# 07_Power_Supply.net
KiCad netlist of a schematic drawn in Altium Designer
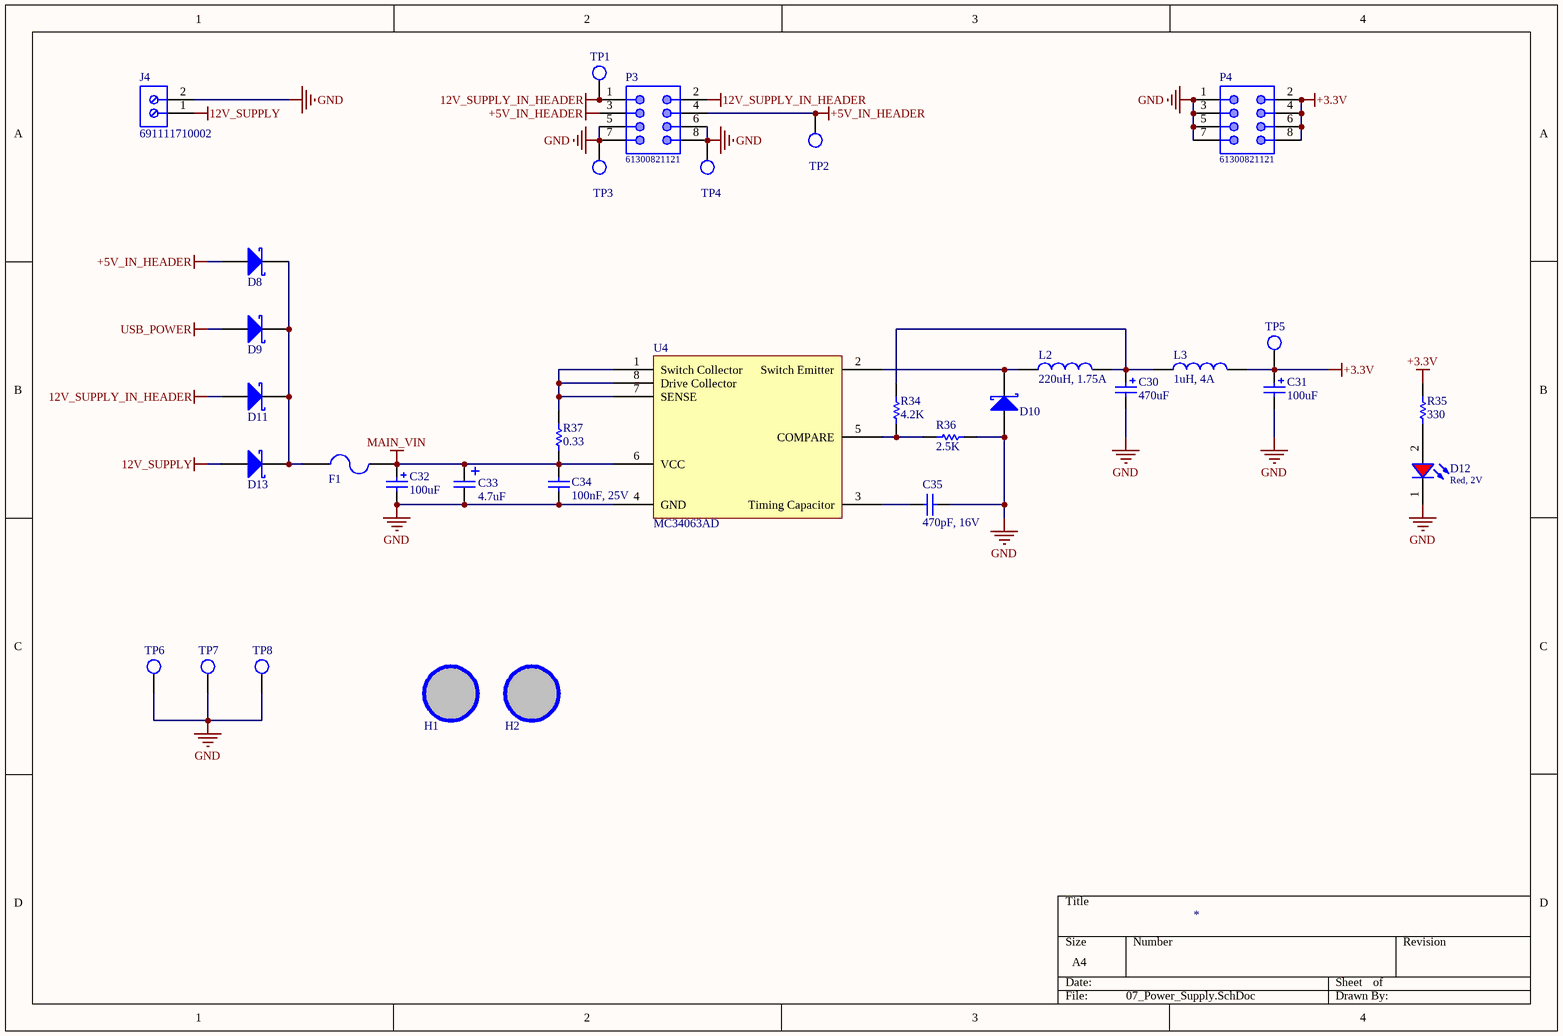
[diagram p0: 07_Power_Supply.SchDoc]

(export (version "E")
  (design (tool "Eeschema 10.0.6"))
  (components
    (comp (ref "C30")
      (value "470uF")
      (footprint "CAP ALU SIZE F")
      (description "Polarized Capacitor (Radial)")
      (fields (field (name "Comment") "Cap Pol SMD"))
      (libsource (lib "PIF_Library") (part "Cap Pol SMD"))
    )
    (comp (ref "C31")
      (value "100uF")
      (footprint "CAP ALU SIZE D")
      (description "Polarized Capacitor (Radial)")
      (fields (field (name "Comment") "Cap Pol SMD"))
      (libsource (lib "PIF_Library") (part "Cap Pol SMD"))
    )
    (comp (ref "C32")
      (value "100uF")
      (footprint "CAP ALU SIZE D")
      (description "Polarized Capacitor (Radial)")
      (fields (field (name "Comment") "Cap Pol SMD"))
      (libsource (lib "PIF_Library") (part "Cap Pol SMD"))
    )
    (comp (ref "C33")
      (value "4.7uF")
      (footprint "CAPMP3216X18N")
      (fields (field (name "Comment") "Tantalum Capacitor"))
      (libsource (lib "MiclsLib") (part "Tantalum Capacitor"))
    )
    (comp (ref "C34")
      (value "100nF, 25V")
      (footprint "WCAP-CSGP_0603_H=0.8mm_Reflow")
      (description "WCAP-CSGP Multilayer Ceramic Chip Capacitor, General Purpose, size 0603, X7R, 100nF, 25V")
      (fields
        (field (name "MANUFACTURER PART NUMBER") "885012206071")
        (field (name "MANUFACTURER") "Wurth Elektronik")
      )
      (libsource (lib "Altium_WCAP-CSGP (rev20a)") (part "885012206071"))
    )
    (comp (ref "C35")
      (value "470pF, 16V")
      (footprint "WCAP-CSGP_0603_H=0.8mm_Reflow")
      (description "WCAP-CSGP Multilayer Ceramic Chip Capacitor, General Purpose, size 0603, NP0, 470pF, 16V")
      (fields
        (field (name "MANUFACTURER PART NUMBER") "885012006027")
        (field (name "MANUFACTURER") "Wurth Elektronik")
      )
      (libsource (lib "Altium_WCAP-CSGP (rev20a)") (part "885012006027"))
    )
    (comp (ref "D8")
      (value "D Schottky")
      (footprint "SS34")
      (description "Schottky Diode")
      (fields (field (name "PUBLISHER") "Altium Limited"))
      (libsource (lib "PIF_Library") (part "D Schottky"))
    )
    (comp (ref "D9")
      (value "D Schottky")
      (footprint "SS34")
      (description "Schottky Diode")
      (fields (field (name "PUBLISHER") "Altium Limited"))
      (libsource (lib "PIF_Library") (part "D Schottky"))
    )
    (comp (ref "D10")
      (value "D Schottky")
      (footprint "SS34")
      (description "Schottky Diode")
      (fields (field (name "PUBLISHER") "Altium Limited"))
      (libsource (lib "PIF_Library") (part "D Schottky"))
    )
    (comp (ref "D11")
      (value "D Schottky")
      (footprint "SS34")
      (description "Schottky Diode")
      (fields (field (name "PUBLISHER") "Altium Limited"))
      (libsource (lib "PIF_Library") (part "D Schottky"))
    )
    (comp (ref "D12")
      (value "Red, 2V")
      (footprint "WL-SMCW_0603_H=0.7mm")
      (description "WL-SMCW SMT Mono-color Chip LED Waterclear, size 0603, Red, 2V, 140deg")
      (fields (field (name "PART NUMBER") "150060RS75000") (field (name "PUBLISHER") "Wurth Elektronik"))
      (libsource (lib "Altium_WL-SMCW (rev20a)") (part "150060RS75000"))
    )
    (comp (ref "D13")
      (value "D Schottky")
      (footprint "SS34")
      (description "Schottky Diode")
      (fields (field (name "PUBLISHER") "Altium Limited"))
      (libsource (lib "PIF_Library") (part "D Schottky"))
    )
    (comp (ref "F1") (value "Fuse") (footprint "FUSE SMD") (libsource (lib "PIF_Library") (part "Fuse")))
    (comp (ref "H1")
      (value "Hole")
      (footprint "LO KHOAN 3MM")
      (description "Hole 3mm")
      (libsource (lib "PIF_Library") (part "Hole"))
    )
    (comp (ref "H2")
      (value "Hole")
      (footprint "LO KHOAN 3MM")
      (description "Hole 3mm")
      (libsource (lib "PIF_Library") (part "Hole"))
    )
    (comp (ref "J4")
      (value "691111710002")
      (footprint "691111710002")
      (description "WR-TBL Serie 111 Horizontal Entry Modular, Pressure Clamp, pitch 5mm, 2p")
      (fields (field (name "PUBLISHER") "Wurth Elektronik"))
      (libsource (lib "691322310002.") (part "691111710002"))
    )
    (comp (ref "L2")
      (value "220uH, 1.75A")
      (footprint "WE-PD2A_5848")
      (description "WE-PD2A SMT Power Inductor, size 5848, 220uH, 0.41A")
      (fields
        (field (name "MANUFACTURER PART NUMBER") "784774222")
        (field (name "MANUFACTURER") "Wurth Elektronik")
      )
      (libsource (lib "Altium_WE-PD2A (rev20a)") (part "784774222"))
    )
    (comp (ref "L3")
      (value "1uH, 4A")
      (footprint "WE-PD2A_4532")
      (description "WE-PD2A SMT Power Inductor, size 4532, 1uH, 4A")
      (fields
        (field (name "MANUFACTURER PART NUMBER") "7847730")
        (field (name "MANUFACTURER") "Wurth Elektronik")
      )
      (libsource (lib "Altium_WE-PD2A (rev20a)") (part "7847730"))
    )
    (comp (ref "P3")
      (value "61300821121")
      (footprint "61300821121")
      (description "WR-PHD Pin Header, THT, pitch 2.54mm, Dual Row, Vertical, 8p")
      (fields (field (name "MANUFACTURER") "Wurth Elektronik"))
      (libsource (lib "Altium_WR-PHD (rev20a)") (part "61300821121"))
    )
    (comp (ref "P4")
      (value "61300821121")
      (footprint "61300821121")
      (description "WR-PHD Pin Header, THT, pitch 2.54mm, Dual Row, Vertical, 8p")
      (fields (field (name "MANUFACTURER") "Wurth Elektronik"))
      (libsource (lib "Altium_WR-PHD (rev20a)") (part "61300821121"))
    )
    (comp (ref "R34")
      (value "4.2K")
      (footprint "RES-SM-0603")
      (description "Resistor")
      (fields (field (name "Comment") "RESISTOR SMD"))
      (libsource (lib "PIF_Library") (part "RESISTOR SMD"))
    )
    (comp (ref "R35")
      (value "330")
      (footprint "RES-SM-0603")
      (description "Resistor")
      (fields (field (name "Comment") "RESISTOR SMD"))
      (libsource (lib "PIF_Library") (part "RESISTOR SMD"))
    )
    (comp (ref "R36")
      (value "2.5K")
      (footprint "RES-SM-0603")
      (description "Resistor")
      (fields (field (name "Comment") "RESISTOR SMD"))
      (libsource (lib "PIF_Library") (part "RESISTOR SMD"))
    )
    (comp (ref "R37")
      (value "0.33")
      (footprint "RES-SM-0805")
      (description "Resistor")
      (fields (field (name "Comment") "RESISTOR SMD"))
      (libsource (lib "PIF_Library") (part "RESISTOR SMD"))
    )
    (comp (ref "TP1") (value "Test point") (footprint "TP") (libsource (lib "MiclsLib") (part "TP")))
    (comp (ref "TP2") (value "Test point") (footprint "TP") (libsource (lib "MiclsLib") (part "TP")))
    (comp (ref "TP3") (value "Test point") (footprint "TP") (libsource (lib "MiclsLib") (part "TP")))
    (comp (ref "TP4") (value "Test point") (footprint "TP") (libsource (lib "MiclsLib") (part "TP")))
    (comp (ref "TP5") (value "Test point") (footprint "TP") (libsource (lib "MiclsLib") (part "TP")))
    (comp (ref "TP6") (value "Test point") (footprint "TP") (libsource (lib "MiclsLib") (part "TP")))
    (comp (ref "TP7") (value "Test point") (footprint "TP") (libsource (lib "MiclsLib") (part "TP")))
    (comp (ref "TP8") (value "Test point") (footprint "TP") (libsource (lib "MiclsLib") (part "TP")))
    (comp (ref "U4")
      (value "MC34063AD")
      (footprint "SOIC127P600X170-8N")
      (description "1.5-A boost, buck, inverting switching regulator, operation from 0°C to 70°C")
      (fields (field (name "MANUFACTURER") "Texas Instruments"))
      (libsource (lib "PowerSupply") (part "MC34063"))
    )
  )
  (nets
    (net (code "1") (name "+3.3V") (class "Default")
      (node (ref "C31") (pin "1") (pinfunction "1_1") (pintype "passive"))
      (node (ref "L3") (pin "2") (pinfunction "2_2") (pintype "passive"))
      (node (ref "P4") (pin "2") (pinfunction "2_2") (pintype "passive"))
      (node (ref "P4") (pin "4") (pinfunction "4_4") (pintype "passive"))
      (node (ref "P4") (pin "6") (pinfunction "6_6") (pintype "passive"))
      (node (ref "P4") (pin "8") (pinfunction "8_8") (pintype "passive"))
      (node (ref "R35") (pin "2") (pinfunction "2_2") (pintype "passive"))
      (node (ref "TP5") (pin "1") (pinfunction "27_1") (pintype "passive"))
    )
    (net (code "2") (name "+5V_IN_HEADER") (class "Default")
      (node (ref "D8") (pin "1") (pinfunction "A_1") (pintype "passive"))
      (node (ref "P3") (pin "3") (pinfunction "3_3") (pintype "passive"))
      (node (ref "P3") (pin "4") (pinfunction "4_4") (pintype "passive"))
      (node (ref "TP2") (pin "1") (pinfunction "27_1") (pintype "passive"))
    )
    (net (code "3") (name "12V_SUPPLY") (class "Default")
      (node (ref "D13") (pin "1") (pinfunction "A_1") (pintype "passive"))
      (node (ref "J4") (pin "1") (pinfunction "1_1") (pintype "passive"))
    )
    (net (code "4") (name "12V_SUPPLY_IN_HEADER") (class "Default")
      (node (ref "D11") (pin "1") (pinfunction "A_1") (pintype "passive"))
      (node (ref "P3") (pin "1") (pinfunction "1_1") (pintype "passive"))
      (node (ref "P3") (pin "2") (pinfunction "2_2") (pintype "passive"))
      (node (ref "TP1") (pin "1") (pinfunction "27_1") (pintype "passive"))
    )
    (net (code "5") (name "GND") (class "Default")
      (node (ref "C30") (pin "2") (pinfunction "2_2") (pintype "passive"))
      (node (ref "C31") (pin "2") (pinfunction "2_2") (pintype "passive"))
      (node (ref "C32") (pin "2") (pinfunction "2_2") (pintype "passive"))
      (node (ref "C33") (pin "2") (pinfunction "2_2") (pintype "passive"))
      (node (ref "C34") (pin "1") (pinfunction "1_1") (pintype "passive"))
      (node (ref "C35") (pin "2") (pinfunction "2_2") (pintype "passive"))
      (node (ref "D10") (pin "1") (pinfunction "A_1") (pintype "passive"))
      (node (ref "D12") (pin "1") (pinfunction "K_1") (pintype "passive"))
      (node (ref "J4") (pin "2") (pinfunction "2_2") (pintype "passive"))
      (node (ref "P3") (pin "5") (pinfunction "5_5") (pintype "passive"))
      (node (ref "P3") (pin "6") (pinfunction "6_6") (pintype "passive"))
      (node (ref "P3") (pin "7") (pinfunction "7_7") (pintype "passive"))
      (node (ref "P3") (pin "8") (pinfunction "8_8") (pintype "passive"))
      (node (ref "P4") (pin "1") (pinfunction "1_1") (pintype "passive"))
      (node (ref "P4") (pin "3") (pinfunction "3_3") (pintype "passive"))
      (node (ref "P4") (pin "5") (pinfunction "5_5") (pintype "passive"))
      (node (ref "P4") (pin "7") (pinfunction "7_7") (pintype "passive"))
      (node (ref "R36") (pin "1") (pinfunction "1_1") (pintype "passive"))
      (node (ref "TP3") (pin "1") (pinfunction "27_1") (pintype "passive"))
      (node (ref "TP4") (pin "1") (pinfunction "27_1") (pintype "passive"))
      (node (ref "TP6") (pin "1") (pinfunction "27_1") (pintype "passive"))
      (node (ref "TP7") (pin "1") (pinfunction "27_1") (pintype "passive"))
      (node (ref "TP8") (pin "1") (pinfunction "27_1") (pintype "passive"))
      (node (ref "U4") (pin "4") (pinfunction "GND_4") (pintype "passive"))
    )
    (net (code "6") (name "MAIN_VIN") (class "Default")
      (node (ref "C32") (pin "1") (pinfunction "1_1") (pintype "passive"))
      (node (ref "C33") (pin "1") (pinfunction "1_1") (pintype "passive"))
      (node (ref "C34") (pin "2") (pinfunction "2_2") (pintype "passive"))
      (node (ref "F1") (pin "2") (pinfunction "2_2") (pintype "passive"))
      (node (ref "R37") (pin "1") (pinfunction "1_1") (pintype "passive"))
      (node (ref "U4") (pin "6") (pinfunction "VCC_6") (pintype "passive"))
    )
    (net (code "7") (name "Net-(C30-Pad1)") (class "Default")
      (node (ref "C30") (pin "1") (pinfunction "1_1") (pintype "passive"))
      (node (ref "L2") (pin "2") (pinfunction "2_2") (pintype "passive"))
      (node (ref "L3") (pin "1") (pinfunction "1_1") (pintype "passive"))
      (node (ref "R34") (pin "2") (pinfunction "2_2") (pintype "passive"))
    )
    (net (code "8") (name "Net-(D10-K)") (class "Default")
      (node (ref "D10") (pin "2") (pinfunction "K_2") (pintype "passive"))
      (node (ref "L2") (pin "1") (pinfunction "1_1") (pintype "passive"))
      (node (ref "U4") (pin "2") (pinfunction "Switch_Emitter_2") (pintype "passive"))
    )
    (net (code "9") (name "Net-(D11-K)") (class "Default")
      (node (ref "D11") (pin "2") (pinfunction "K_2") (pintype "passive"))
      (node (ref "D13") (pin "2") (pinfunction "K_2") (pintype "passive"))
      (node (ref "D8") (pin "2") (pinfunction "K_2") (pintype "passive"))
      (node (ref "D9") (pin "2") (pinfunction "K_2") (pintype "passive"))
      (node (ref "F1") (pin "1") (pinfunction "1_1") (pintype "passive"))
    )
    (net (code "10") (name "Net-(D12-A)") (class "Default")
      (node (ref "D12") (pin "2") (pinfunction "A_2") (pintype "passive"))
      (node (ref "R35") (pin "1") (pinfunction "1_1") (pintype "passive"))
    )
    (net (code "11") (name "Net-(U4-COMPARE)") (class "Default")
      (node (ref "R34") (pin "1") (pinfunction "1_1") (pintype "passive"))
      (node (ref "R36") (pin "2") (pinfunction "2_2") (pintype "passive"))
      (node (ref "U4") (pin "5") (pinfunction "COMPARE_5") (pintype "passive"))
    )
    (net (code "12") (name "Net-(U4-Drive_Collector)") (class "Default")
      (node (ref "R37") (pin "2") (pinfunction "2_2") (pintype "passive"))
      (node (ref "U4") (pin "1") (pinfunction "Switch_Collector_1") (pintype "passive"))
      (node (ref "U4") (pin "7") (pinfunction "SENSE_7") (pintype "passive"))
      (node (ref "U4") (pin "8") (pinfunction "Drive_Collector_8") (pintype "passive"))
    )
    (net (code "13") (name "Net-(U4-Timing_Capacitor)") (class "Default")
      (node (ref "C35") (pin "1") (pinfunction "1_1") (pintype "passive"))
      (node (ref "U4") (pin "3") (pinfunction "Timing_Capacitor_3") (pintype "passive"))
    )
    (net (code "14") (name "USB_POWER") (class "Default")
      (node (ref "D9") (pin "1") (pinfunction "A_1") (pintype "passive"))
    )
    (net (code "15") (name "unconnected-(H1-Pad1)") (class "Default")
      (node (ref "H1") (pin "1") (pinfunction "1_1") (pintype "passive"))
    )
    (net (code "16") (name "unconnected-(H2-Pad1)") (class "Default")
      (node (ref "H2") (pin "1") (pinfunction "1_1") (pintype "passive"))
    )
  )
)
